# I2C_extender_1.net
KiCad netlist of a schematic drawn in Altium Designer
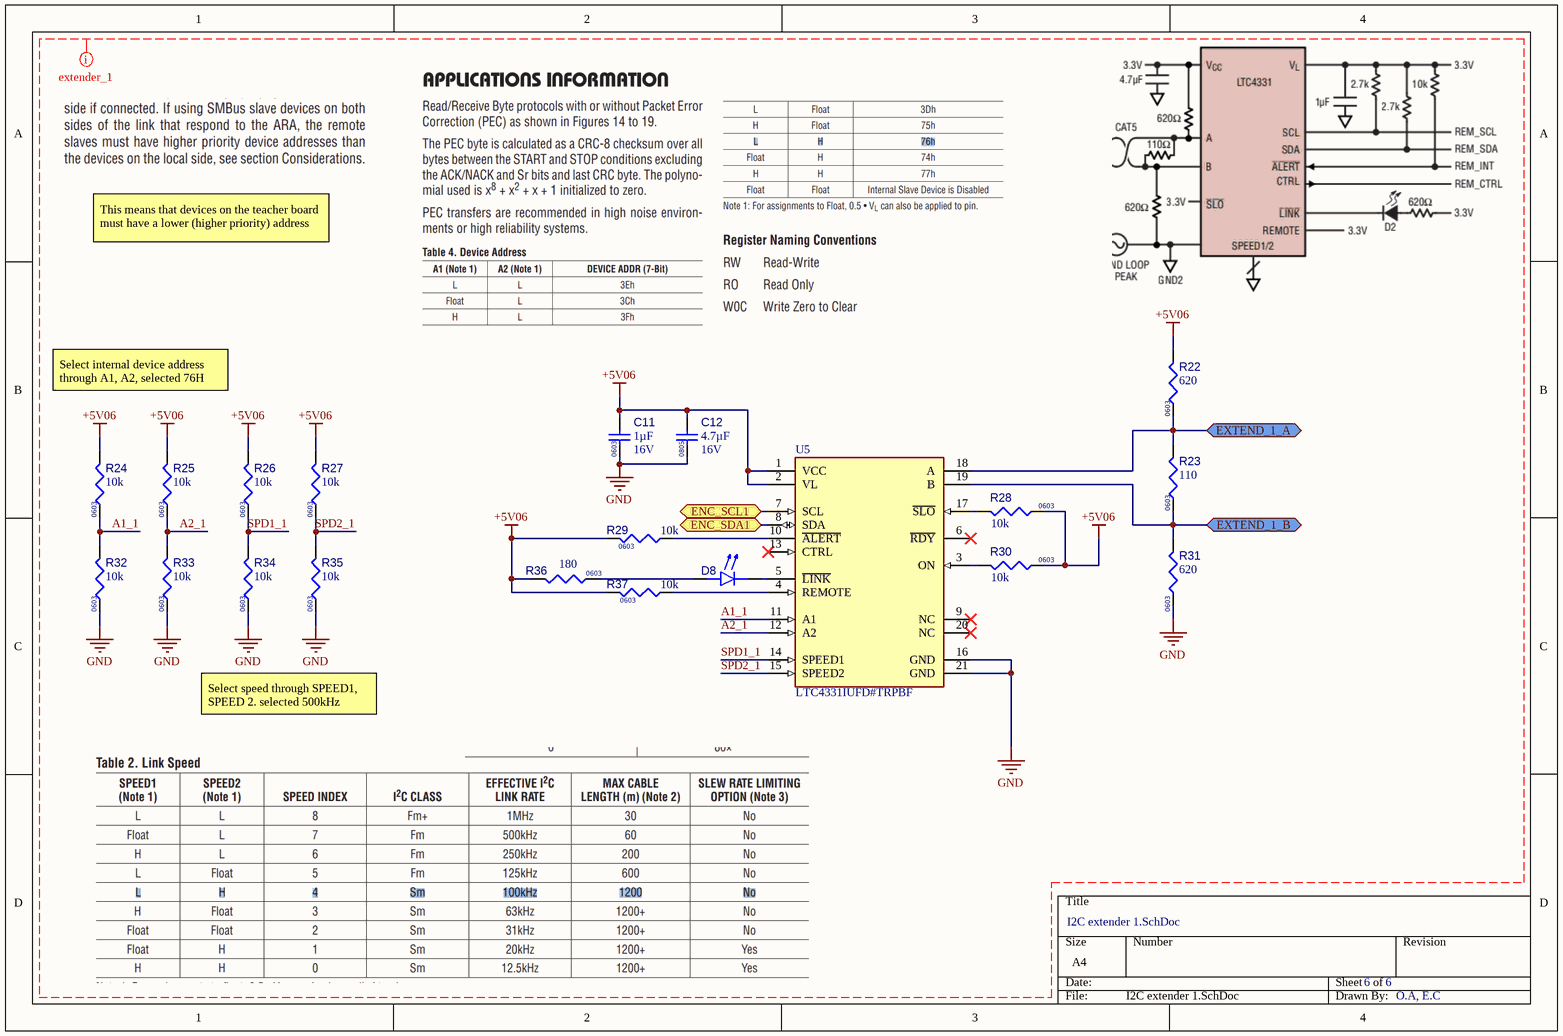
[diagram p0: I2C extender 1.SchDoc]

(export (version "E")
  (design (tool "Eeschema 10.0.6"))
  (components
    (comp (ref "C11")
      (value "1µF")
      (footprint "CAPC1608X90X35NL15T15")
      (description "Chip Capacitor, 1 uF, +/- 10%, 16 V, 0603 (1608 Metric)")
      (fields
        (field (name "CASE/PACKAGE") "0603")
        (field (name "VOLTAGE RATING") "16V")
        (field (name "TOLERANCE") "10%")
        (field (name "Comment") "Capacitor 1uF +/- 10% 16V 0603")
      )
      (libsource (lib "hawaiirobotics") (part "CAP-NP-2"))
    )
    (comp (ref "C12")
      (value "4.7µF")
      (footprint "CL21A475KOFNNNE-Footprint-1")
      (fields
        (field (name "CASE/PACKAGE") "0805")
        (field (name "RATED DC VOLTAGE (URDC)") "16V")
        (field (name "Comment") "CL21A475KOFNNNE")
      )
      (libsource (lib "hawaiirobotics") (part "CAP-NP-2"))
    )
    (comp (ref "D8")
      (value "150060YS75000")
      (footprint "WL-SMCW_0603_150060xx75000")
      (description "Single Color LED, Yellow, Water Clear, 1.1mm")
      (libsource (lib "hawaiirobotics") (part "DIODE-LED-2"))
    )
    (comp (ref "R22")
      (value "620")
      (footprint "RC0603JR-0720KL-Footprint-1")
      (fields
        (field (name "POWER") "100mW")
        (field (name "CASE/PACKAGE") "0603")
        (field (name "TOLERANCE") "1%")
        (field (name "Comment") "RC0603FR-07620RL")
      )
      (libsource (lib "hawaiirobotics") (part "RES-2"))
    )
    (comp (ref "R23")
      (value "110")
      (footprint "RC0603JR-0720KL-Footprint-1")
      (fields
        (field (name "TOLERANCE") "1%")
        (field (name "POWER") "100mW")
        (field (name "CASE/PACKAGE") "0603")
        (field (name "Comment") "RC0603FR-07110RL")
      )
      (libsource (lib "hawaiirobotics") (part "RES-2"))
    )
    (comp (ref "R24")
      (value "10k")
      (footprint "RESC1608X55X25NL10T15")
      (description "Chip Resistor, 10 KOhm, +/- 1%, 01 W, -55 to 155 degC, 0603 (1608 Metric)")
      (fields
        (field (name "CASE/PACKAGE") "0603")
        (field (name "POWER") "100mW")
        (field (name "TOLERANCE") "1%")
      )
      (libsource (lib "hawaiirobotics") (part "RES-2"))
    )
    (comp (ref "R25")
      (value "10k")
      (footprint "RESC1608X55X25NL10T15")
      (description "Chip Resistor, 10 KOhm, +/- 1%, 01 W, -55 to 155 degC, 0603 (1608 Metric)")
      (fields
        (field (name "CASE/PACKAGE") "0603")
        (field (name "POWER") "100mW")
        (field (name "TOLERANCE") "1%")
      )
      (libsource (lib "hawaiirobotics") (part "RES-2"))
    )
    (comp (ref "R26")
      (value "10k")
      (footprint "RESC1608X55X25NL10T15")
      (description "Chip Resistor, 10 KOhm, +/- 1%, 01 W, -55 to 155 degC, 0603 (1608 Metric)")
      (fields
        (field (name "CASE/PACKAGE") "0603")
        (field (name "POWER") "100mW")
        (field (name "TOLERANCE") "1%")
      )
      (libsource (lib "hawaiirobotics") (part "RES-2"))
    )
    (comp (ref "R27")
      (value "10k")
      (footprint "RESC1608X55X25NL10T15")
      (description "Chip Resistor, 10 KOhm, +/- 1%, 01 W, -55 to 155 degC, 0603 (1608 Metric)")
      (fields
        (field (name "CASE/PACKAGE") "0603")
        (field (name "POWER") "100mW")
        (field (name "TOLERANCE") "1%")
      )
      (libsource (lib "hawaiirobotics") (part "RES-2"))
    )
    (comp (ref "R28")
      (value "10k")
      (footprint "RESC1608X55X25NL10T15")
      (description "Chip Resistor, 10 KOhm, +/- 1%, 01 W, -55 to 155 degC, 0603 (1608 Metric)")
      (fields
        (field (name "CASE/PACKAGE") "0603")
        (field (name "POWER") "100mW")
        (field (name "TOLERANCE") "1%")
      )
      (libsource (lib "hawaiirobotics") (part "RES-2"))
    )
    (comp (ref "R29")
      (value "10k")
      (footprint "RESC1608X55X25NL10T15")
      (description "Chip Resistor, 10 KOhm, +/- 1%, 01 W, -55 to 155 degC, 0603 (1608 Metric)")
      (fields
        (field (name "CASE/PACKAGE") "0603")
        (field (name "POWER") "100mW")
        (field (name "TOLERANCE") "1%")
      )
      (libsource (lib "hawaiirobotics") (part "RES-2"))
    )
    (comp (ref "R30")
      (value "10k")
      (footprint "RESC1608X55X25NL10T15")
      (description "Chip Resistor, 10 KOhm, +/- 1%, 01 W, -55 to 155 degC, 0603 (1608 Metric)")
      (fields
        (field (name "CASE/PACKAGE") "0603")
        (field (name "POWER") "100mW")
        (field (name "TOLERANCE") "1%")
      )
      (libsource (lib "hawaiirobotics") (part "RES-2"))
    )
    (comp (ref "R31")
      (value "620")
      (footprint "RC0603JR-0720KL-Footprint-1")
      (fields
        (field (name "POWER") "100mW")
        (field (name "CASE/PACKAGE") "0603")
        (field (name "TOLERANCE") "1%")
        (field (name "Comment") "RC0603FR-07620RL")
      )
      (libsource (lib "hawaiirobotics") (part "RES-2"))
    )
    (comp (ref "R32")
      (value "10k")
      (footprint "RESC1608X55X25NL10T15")
      (description "Chip Resistor, 10 KOhm, +/- 1%, 01 W, -55 to 155 degC, 0603 (1608 Metric)")
      (fields
        (field (name "CASE/PACKAGE") "0603")
        (field (name "POWER") "100mW")
        (field (name "TOLERANCE") "1%")
      )
      (libsource (lib "hawaiirobotics") (part "RES-2"))
    )
    (comp (ref "R33")
      (value "10k")
      (footprint "RESC1608X55X25NL10T15")
      (description "Chip Resistor, 10 KOhm, +/- 1%, 01 W, -55 to 155 degC, 0603 (1608 Metric)")
      (fields
        (field (name "CASE/PACKAGE") "0603")
        (field (name "POWER") "100mW")
        (field (name "TOLERANCE") "1%")
      )
      (libsource (lib "hawaiirobotics") (part "RES-2"))
    )
    (comp (ref "R34")
      (value "10k")
      (footprint "RESC1608X55X25NL10T15")
      (description "Chip Resistor, 10 KOhm, +/- 1%, 01 W, -55 to 155 degC, 0603 (1608 Metric)")
      (fields
        (field (name "CASE/PACKAGE") "0603")
        (field (name "POWER") "100mW")
        (field (name "TOLERANCE") "1%")
      )
      (libsource (lib "hawaiirobotics") (part "RES-2"))
    )
    (comp (ref "R35")
      (value "10k")
      (footprint "RESC1608X55X25NL10T15")
      (description "Chip Resistor, 10 KOhm, +/- 1%, 01 W, -55 to 155 degC, 0603 (1608 Metric)")
      (fields
        (field (name "CASE/PACKAGE") "0603")
        (field (name "POWER") "100mW")
        (field (name "TOLERANCE") "1%")
      )
      (libsource (lib "hawaiirobotics") (part "RES-2"))
    )
    (comp (ref "R36")
      (value "180")
      (footprint "RESC0603(1608)_N")
      (fields
        (field (name "TOLERANCE") "5%")
        (field (name "CASE/PACKAGE") "0603")
        (field (name "POWER") "100mW")
        (field (name "Comment") "RC0603JR-07180RL")
      )
      (libsource (lib "hawaiirobotics") (part "RES-2"))
    )
    (comp (ref "R37")
      (value "10k")
      (footprint "RESC1608X55X25NL10T15")
      (description "Chip Resistor, 10 KOhm, +/- 1%, 01 W, -55 to 155 degC, 0603 (1608 Metric)")
      (fields
        (field (name "CASE/PACKAGE") "0603")
        (field (name "POWER") "100mW")
        (field (name "TOLERANCE") "1%")
      )
      (libsource (lib "hawaiirobotics") (part "RES-2"))
    )
    (comp (ref "U5")
      (value "LTC4331IUFD#TRPBF")
      (footprint "FP-UFD-20-05-08-1711-IPC_C")
      (description "Interface Circuit, CMOS, PQCC20")
      (libsource (lib "hawaiirobotics") (part "90934f5fbb90c4d29cf3ee1665de234"))
    )
  )
  (nets
    (net (code "1") (name "+5V06") (class "Default")
      (node (ref "C11") (pin "2") (pinfunction "2_2") (pintype "passive"))
      (node (ref "C12") (pin "2") (pinfunction "2_2") (pintype "passive"))
      (node (ref "R22") (pin "2") (pinfunction "2_2") (pintype "passive"))
      (node (ref "R24") (pin "2") (pinfunction "2_2") (pintype "passive"))
      (node (ref "R25") (pin "2") (pinfunction "2_2") (pintype "passive"))
      (node (ref "R26") (pin "2") (pinfunction "2_2") (pintype "passive"))
      (node (ref "R27") (pin "2") (pinfunction "2_2") (pintype "passive"))
      (node (ref "R28") (pin "1") (pinfunction "1_1") (pintype "passive"))
      (node (ref "R29") (pin "1") (pinfunction "1_1") (pintype "passive"))
      (node (ref "R30") (pin "1") (pinfunction "1_1") (pintype "passive"))
      (node (ref "R36") (pin "2") (pinfunction "2_2") (pintype "passive"))
      (node (ref "R37") (pin "1") (pinfunction "1_1") (pintype "passive"))
      (node (ref "U5") (pin "1") (pinfunction "VCC_1") (pintype "power_in"))
      (node (ref "U5") (pin "2") (pinfunction "VL_2") (pintype "power_in"))
    )
    (net (code "2") (name "/A1_1") (class "Default")
      (node (ref "R24") (pin "1") (pinfunction "1_1") (pintype "passive"))
      (node (ref "R32") (pin "2") (pinfunction "2_2") (pintype "passive"))
      (node (ref "U5") (pin "11") (pinfunction "A1_11") (pintype "input"))
    )
    (net (code "3") (name "/A2_1") (class "Default")
      (node (ref "R25") (pin "1") (pinfunction "1_1") (pintype "passive"))
      (node (ref "R33") (pin "2") (pinfunction "2_2") (pintype "passive"))
      (node (ref "U5") (pin "12") (pinfunction "A2_12") (pintype "input"))
    )
    (net (code "4") (name "/ENC_SCL1") (class "Default")
      (node (ref "U5") (pin "7") (pinfunction "SCL_7") (pintype "input"))
    )
    (net (code "5") (name "/ENC_SDA1") (class "Default")
      (node (ref "U5") (pin "8") (pinfunction "SDA_8") (pintype "bidirectional"))
    )
    (net (code "6") (name "/EXTEND_1_A") (class "Default")
      (node (ref "R22") (pin "1") (pinfunction "1_1") (pintype "passive"))
      (node (ref "R23") (pin "2") (pinfunction "2_2") (pintype "passive"))
      (node (ref "U5") (pin "18") (pinfunction "A_18") (pintype "tri_state"))
    )
    (net (code "7") (name "/EXTEND_1_B") (class "Default")
      (node (ref "R23") (pin "1") (pinfunction "1_1") (pintype "passive"))
      (node (ref "R31") (pin "2") (pinfunction "2_2") (pintype "passive"))
      (node (ref "U5") (pin "19") (pinfunction "B_19") (pintype "tri_state"))
    )
    (net (code "8") (name "/SPD1_1") (class "Default")
      (node (ref "R26") (pin "1") (pinfunction "1_1") (pintype "passive"))
      (node (ref "R34") (pin "2") (pinfunction "2_2") (pintype "passive"))
      (node (ref "U5") (pin "14") (pinfunction "SPEED1_14") (pintype "input"))
    )
    (net (code "9") (name "/SPD2_1") (class "Default")
      (node (ref "R27") (pin "1") (pinfunction "1_1") (pintype "passive"))
      (node (ref "R35") (pin "2") (pinfunction "2_2") (pintype "passive"))
      (node (ref "U5") (pin "15") (pinfunction "SPEED2_15") (pintype "input"))
    )
    (net (code "10") (name "GND") (class "Default")
      (node (ref "C11") (pin "1") (pinfunction "1_1") (pintype "passive"))
      (node (ref "C12") (pin "1") (pinfunction "1_1") (pintype "passive"))
      (node (ref "R31") (pin "1") (pinfunction "1_1") (pintype "passive"))
      (node (ref "R32") (pin "1") (pinfunction "1_1") (pintype "passive"))
      (node (ref "R33") (pin "1") (pinfunction "1_1") (pintype "passive"))
      (node (ref "R34") (pin "1") (pinfunction "1_1") (pintype "passive"))
      (node (ref "R35") (pin "1") (pinfunction "1_1") (pintype "passive"))
      (node (ref "U5") (pin "16") (pinfunction "GND_16") (pintype "power_in"))
      (node (ref "U5") (pin "21") (pinfunction "GND_21") (pintype "power_in"))
    )
    (net (code "11") (name "Net-(D8-A)") (class "Default")
      (node (ref "D8") (pin "2") (pinfunction "A_2") (pintype "passive"))
      (node (ref "R36") (pin "1") (pinfunction "1_1") (pintype "passive"))
    )
    (net (code "12") (name "Net-(D8-K)") (class "Default")
      (node (ref "D8") (pin "1") (pinfunction "K_1") (pintype "passive"))
      (node (ref "U5") (pin "5") (pinfunction "~{LINK}_5") (pintype "open_collector"))
    )
    (net (code "13") (name "Net-(U5-ON)") (class "Default")
      (node (ref "R30") (pin "2") (pinfunction "2_2") (pintype "passive"))
      (node (ref "U5") (pin "3") (pinfunction "ON_3") (pintype "input"))
    )
    (net (code "14") (name "Net-(U5-REMOTE)") (class "Default")
      (node (ref "R37") (pin "2") (pinfunction "2_2") (pintype "passive"))
      (node (ref "U5") (pin "4") (pinfunction "REMOTE_4") (pintype "input"))
    )
    (net (code "15") (name "Net-(U5-~{ALERT})") (class "Default")
      (node (ref "R29") (pin "2") (pinfunction "2_2") (pintype "passive"))
      (node (ref "U5") (pin "10") (pinfunction "~{ALERT}_10") (pintype "open_collector"))
    )
    (net (code "16") (name "Net-(U5-~{SLO})") (class "Default")
      (node (ref "R28") (pin "2") (pinfunction "2_2") (pintype "passive"))
      (node (ref "U5") (pin "17") (pinfunction "~{SLO}_17") (pintype "input"))
    )
    (net (code "17") (name "unconnected-(U5-CTRL-Pad13)") (class "Default")
      (node (ref "U5") (pin "13") (pinfunction "CTRL_13") (pintype "input+no_connect"))
    )
    (net (code "18") (name "unconnected-(U5-NC-Pad9)") (class "Default")
      (node (ref "U5") (pin "9") (pinfunction "NC_9") (pintype "passive+no_connect"))
    )
    (net (code "19") (name "unconnected-(U5-NC-Pad20)") (class "Default")
      (node (ref "U5") (pin "20") (pinfunction "NC_20") (pintype "passive+no_connect"))
    )
    (net (code "20") (name "unconnected-(U5-~{RDY}-Pad6)") (class "Default")
      (node (ref "U5") (pin "6") (pinfunction "~{RDY}_6") (pintype "open_collector+no_connect"))
    )
  )
)
